# AFE_1.net
KiCad netlist of a schematic drawn in Altium Designer
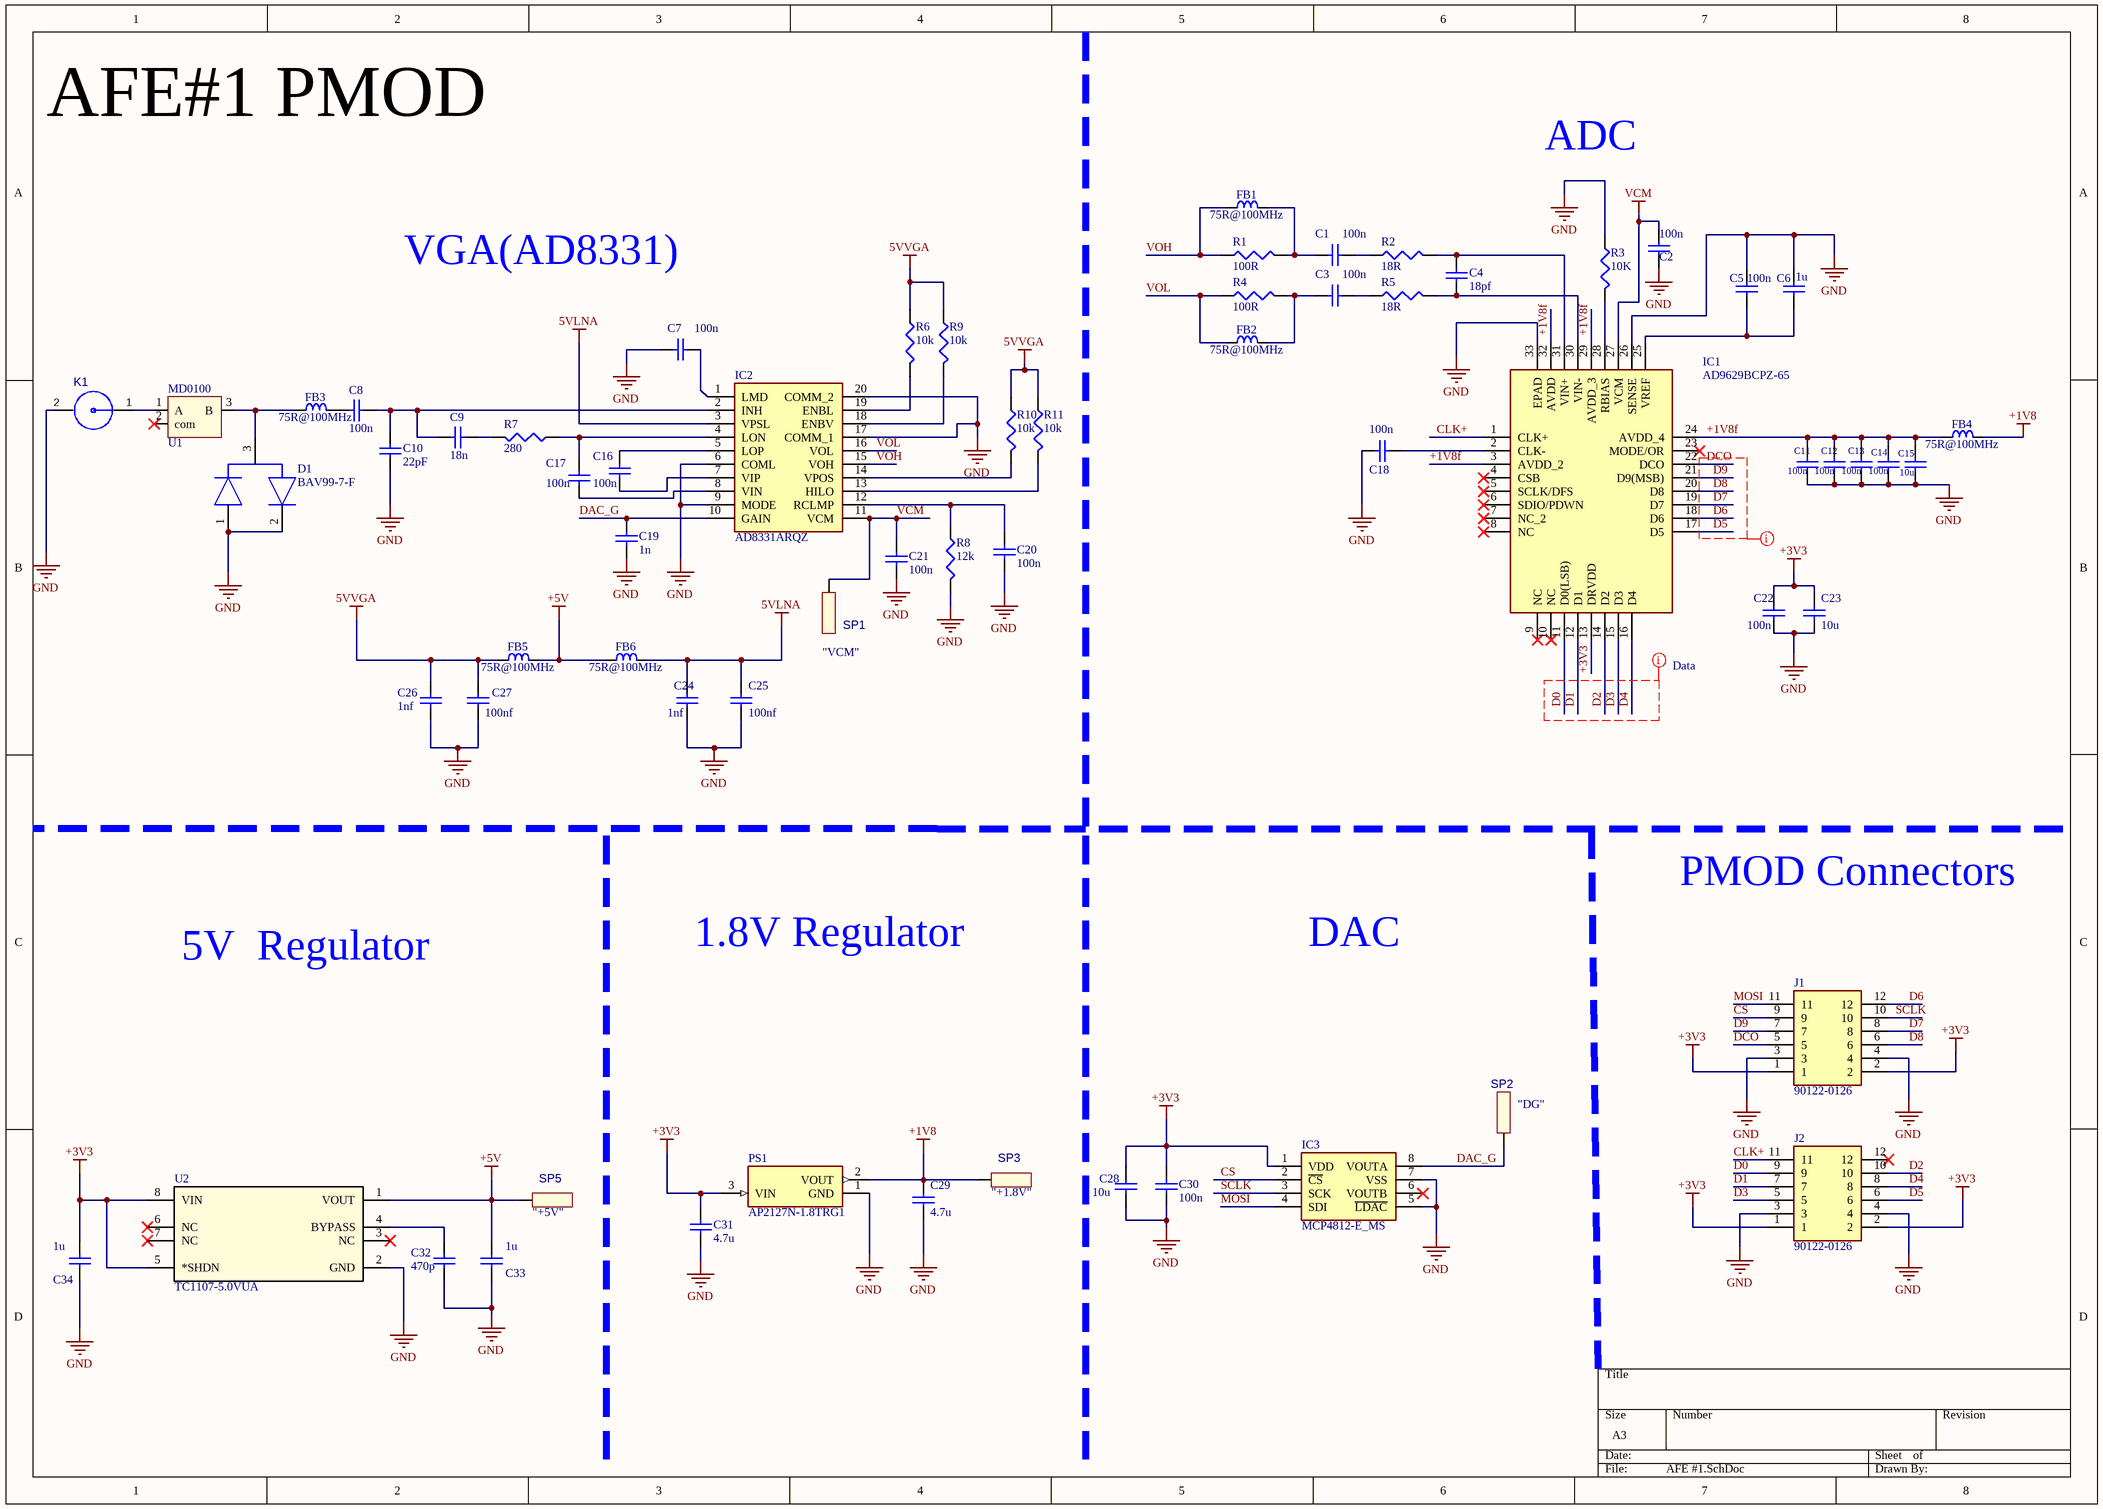
[diagram p0: AFE #1.SchDoc]

(export (version "E")
  (design (tool "Eeschema 10.0.6"))
  (components
    (comp (ref "C1")
      (value "100n")
      (footprint "0402_C")
      (description "Capacitor  0402 inch")
      (fields (field (name "Comment") "cap0402") (field (name "PUBLISHER") "Altium Limited"))
      (libsource (lib "alt2017") (part "cap0603"))
    )
    (comp (ref "C2")
      (value "100n")
      (footprint "0402_C")
      (description "Capacitor  0402 inch")
      (fields (field (name "Comment") "cap0402") (field (name "PUBLISHER") "Altium Limited"))
      (libsource (lib "alt2017") (part "cap0603"))
    )
    (comp (ref "C3")
      (value "100n")
      (footprint "0402_C")
      (description "Capacitor  0402 inch")
      (fields (field (name "Comment") "cap0402") (field (name "PUBLISHER") "Altium Limited"))
      (libsource (lib "alt2017") (part "cap0603"))
    )
    (comp (ref "C4")
      (value "18pf")
      (footprint "0402_C")
      (description "Capacitor  0402 inch")
      (fields (field (name "Comment") "cap0402") (field (name "PUBLISHER") "Altium Limited"))
      (libsource (lib "alt2017") (part "cap0603"))
    )
    (comp (ref "C5")
      (value "100n")
      (footprint "0402_C")
      (description "Capacitor  0402 inch")
      (fields (field (name "Comment") "cap0402") (field (name "PUBLISHER") "Altium Limited"))
      (libsource (lib "alt2017") (part "cap0603"))
    )
    (comp (ref "C6")
      (value "1u")
      (footprint "SM0603 _3D_cap")
      (description "Capacitor  0603 inch")
      (fields (field (name "Comment") "cap0603") (field (name "PUBLISHER") "Altium Limited"))
      (libsource (lib "alt2017") (part "cap0603"))
    )
    (comp (ref "C7")
      (value "100n")
      (footprint "0402_C")
      (description "Capacitor  0402 inch")
      (fields (field (name "Comment") "cap0402") (field (name "PUBLISHER") "Altium Limited"))
      (libsource (lib "alt2017") (part "cap0603"))
    )
    (comp (ref "C8")
      (value "100n")
      (footprint "0402_C")
      (description "Capacitor  0402 inch")
      (fields (field (name "Comment") "cap0402") (field (name "PUBLISHER") "Altium Limited"))
      (libsource (lib "alt2017") (part "cap0603"))
    )
    (comp (ref "C9")
      (value "18n")
      (footprint "0402_C")
      (description "Capacitor  0402 inch")
      (fields (field (name "Comment") "cap0402") (field (name "PUBLISHER") "Altium Limited"))
      (libsource (lib "alt2017") (part "cap0603"))
    )
    (comp (ref "C10")
      (value "22pF")
      (footprint "0402_C")
      (description "Capacitor  0402 inch")
      (fields (field (name "Comment") "cap0402") (field (name "PUBLISHER") "Altium Limited"))
      (libsource (lib "alt2017") (part "cap0603"))
    )
    (comp (ref "C11")
      (value "100n")
      (footprint "0402_C")
      (description "Capacitor  0402 inch")
      (fields (field (name "Comment") "cap0402") (field (name "PUBLISHER") "Altium Limited"))
      (libsource (lib "alt2017") (part "cap0603"))
    )
    (comp (ref "C12")
      (value "100n")
      (footprint "0402_C")
      (description "Capacitor  0402 inch")
      (fields (field (name "Comment") "cap0402") (field (name "PUBLISHER") "Altium Limited"))
      (libsource (lib "alt2017") (part "cap0603"))
    )
    (comp (ref "C13")
      (value "100n")
      (footprint "0402_C")
      (description "Capacitor  0402 inch")
      (fields (field (name "Comment") "cap0402") (field (name "PUBLISHER") "Altium Limited"))
      (libsource (lib "alt2017") (part "cap0603"))
    )
    (comp (ref "C14")
      (value "100n")
      (footprint "0402_C")
      (description "Capacitor  0402 inch")
      (fields (field (name "Comment") "cap0402") (field (name "PUBLISHER") "Altium Limited"))
      (libsource (lib "alt2017") (part "cap0603"))
    )
    (comp (ref "C15")
      (value "10u")
      (footprint "SM0603 _3D_cap")
      (description "Capacitor  0402 inch")
      (fields (field (name "Comment") "cap0402") (field (name "PUBLISHER") "Altium Limited"))
      (libsource (lib "alt2017") (part "cap0603"))
    )
    (comp (ref "C16")
      (value "100n")
      (footprint "0402_C")
      (description "Capacitor  0402 inch")
      (fields (field (name "Comment") "cap0402") (field (name "PUBLISHER") "Altium Limited"))
      (libsource (lib "alt2017") (part "cap0603"))
    )
    (comp (ref "C17")
      (value "100n")
      (footprint "0402_C")
      (description "Capacitor  0402 inch")
      (fields (field (name "Comment") "cap0402") (field (name "PUBLISHER") "Altium Limited"))
      (libsource (lib "alt2017") (part "cap0603"))
    )
    (comp (ref "C18")
      (value "100n")
      (footprint "0402_C")
      (description "Capacitor  0402 inch")
      (fields (field (name "Comment") "cap0402") (field (name "PUBLISHER") "Altium Limited"))
      (libsource (lib "alt2017") (part "cap0603"))
    )
    (comp (ref "C19")
      (value "1n")
      (footprint "0402_C")
      (description "Capacitor  0402 inch")
      (fields (field (name "Comment") "cap0402") (field (name "PUBLISHER") "Altium Limited"))
      (libsource (lib "alt2017") (part "cap0603"))
    )
    (comp (ref "C20")
      (value "100n")
      (footprint "0402_C")
      (description "Capacitor  0402 inch")
      (fields (field (name "Comment") "cap0402") (field (name "PUBLISHER") "Altium Limited"))
      (libsource (lib "alt2017") (part "cap0603"))
    )
    (comp (ref "C21")
      (value "100n")
      (footprint "0402_C")
      (description "Capacitor  0402 inch")
      (fields (field (name "Comment") "cap0402") (field (name "PUBLISHER") "Altium Limited"))
      (libsource (lib "alt2017") (part "cap0603"))
    )
    (comp (ref "C22")
      (value "100n")
      (footprint "0402_C")
      (description "Capacitor  0402 inch")
      (fields (field (name "Comment") "cap0402") (field (name "PUBLISHER") "Altium Limited"))
      (libsource (lib "alt2017") (part "cap0603"))
    )
    (comp (ref "C23")
      (value "10u")
      (footprint "SM0603 _3D_cap")
      (description "Capacitor  0603 inch")
      (fields (field (name "Comment") "cap0603") (field (name "PUBLISHER") "Altium Limited"))
      (libsource (lib "alt2017") (part "cap0603"))
    )
    (comp (ref "C24")
      (value "1nf")
      (footprint "0402_C")
      (description "Capacitor  0603 inch")
      (fields (field (name "Comment") "cap0402") (field (name "PUBLISHER") "Altium Limited"))
      (libsource (lib "alt2017") (part "cap0603"))
    )
    (comp (ref "C25")
      (value "100nf")
      (footprint "0402_C")
      (description "Capacitor  0402 inch")
      (fields (field (name "Comment") "cap0402") (field (name "PUBLISHER") "Altium Limited"))
      (libsource (lib "alt2017") (part "cap0603"))
    )
    (comp (ref "C26")
      (value "1nf")
      (footprint "0402_C")
      (description "Capacitor  0603 inch")
      (fields (field (name "Comment") "cap0402") (field (name "PUBLISHER") "Altium Limited"))
      (libsource (lib "alt2017") (part "cap0603"))
    )
    (comp (ref "C27")
      (value "100nf")
      (footprint "0402_C")
      (description "Capacitor  0402 inch")
      (fields (field (name "Comment") "cap0402") (field (name "PUBLISHER") "Altium Limited"))
      (libsource (lib "alt2017") (part "cap0603"))
    )
    (comp (ref "C28")
      (value "10u")
      (footprint "SM0603 _3D_cap")
      (description "Capacitor  0603 inch")
      (fields (field (name "Comment") "cap0603") (field (name "PUBLISHER") "Altium Limited"))
      (libsource (lib "alt2017") (part "cap0603"))
    )
    (comp (ref "C29")
      (value "4.7u")
      (footprint "SM0603 _3D_cap")
      (description "Capacitor  0603 inch")
      (fields (field (name "Comment") "cap0603") (field (name "PUBLISHER") "Altium Limited"))
      (libsource (lib "alt2017") (part "cap0603"))
    )
    (comp (ref "C30")
      (value "100n")
      (footprint "0402_C")
      (description "Capacitor  0402 inch")
      (fields (field (name "Comment") "cap0402") (field (name "PUBLISHER") "Altium Limited"))
      (libsource (lib "alt2017") (part "cap0603"))
    )
    (comp (ref "C31")
      (value "4.7u")
      (footprint "SM0603 _3D_cap")
      (description "Capacitor  0603 inch")
      (fields (field (name "Comment") "cap0603") (field (name "PUBLISHER") "Altium Limited"))
      (libsource (lib "alt2017") (part "cap0603"))
    )
    (comp (ref "C32")
      (value "470p")
      (footprint "0402_C")
      (description "Capacitor  0402 inch")
      (fields (field (name "Comment") "cap0402") (field (name "PUBLISHER") "Altium Limited"))
      (libsource (lib "alt2017") (part "cap0603"))
    )
    (comp (ref "C33")
      (value "1u")
      (footprint "SM0603 _3D_cap")
      (description "Capacitor  0603 inch")
      (fields (field (name "Comment") "cap0603") (field (name "PUBLISHER") "Altium Limited"))
      (libsource (lib "alt2017") (part "cap0603"))
    )
    (comp (ref "C34")
      (value "1u")
      (footprint "SM0603 _3D_cap")
      (description "Capacitor  0603 inch")
      (fields (field (name "Comment") "cap0603") (field (name "PUBLISHER") "Altium Limited"))
      (libsource (lib "alt2017") (part "cap0603"))
    )
    (comp (ref "D1")
      (value "BAV99-7-F")
      (footprint "SOT95P240X120-3N")
      (description "Diode")
      (fields (field (name "MOUSER PART NUMBER") "621-BAV99-F"))
      (libsource (lib "*") (part "BAV99-7-F"))
    )
    (comp (ref "FB1")
      (value "75R@100MHz")
      (footprint "SM0603_3D_res")
      (description "chip inductance 0603")
      (fields
        (field (name "PART NUMBER") "IND0805_MURATA_BLM21BB750SN1D")
        (field (name "POWER") "700mA")
        (field (name "AUTHOR") "S. Jafar")
      )
      (libsource (lib "alt_vovan") (part "chip inductance 0603"))
    )
    (comp (ref "FB2")
      (value "75R@100MHz")
      (footprint "SM0603_3D_res")
      (description "chip inductance 0603")
      (fields
        (field (name "PART NUMBER") "IND0805_MURATA_BLM21BB750SN1D")
        (field (name "POWER") "700mA")
        (field (name "AUTHOR") "S. Jafar")
      )
      (libsource (lib "alt_vovan") (part "chip inductance 0603"))
    )
    (comp (ref "FB3")
      (value "75R@100MHz")
      (footprint "SM0603_3D_res")
      (description "chip inductance 0603")
      (fields
        (field (name "PART NUMBER") "IND0805_MURATA_BLM21BB750SN1D")
        (field (name "POWER") "700mA")
        (field (name "AUTHOR") "S. Jafar")
      )
      (libsource (lib "alt_vovan") (part "chip inductance 0603"))
    )
    (comp (ref "FB4")
      (value "75R@100MHz")
      (footprint "SM0603_3D_res")
      (description "chip inductance 0603")
      (fields
        (field (name "PART NUMBER") "IND0805_MURATA_BLM21BB750SN1D")
        (field (name "POWER") "700mA")
        (field (name "AUTHOR") "S. Jafar")
      )
      (libsource (lib "alt_vovan") (part "chip inductance 0603"))
    )
    (comp (ref "FB5")
      (value "75R@100MHz")
      (footprint "SM0603_3D_res")
      (description "chip inductance 0603")
      (fields
        (field (name "PART NUMBER") "IND0805_MURATA_BLM21BB750SN1D")
        (field (name "POWER") "700mA")
        (field (name "AUTHOR") "S. Jafar")
      )
      (libsource (lib "alt_vovan") (part "chip inductance 0603"))
    )
    (comp (ref "FB6")
      (value "75R@100MHz")
      (footprint "SM0603_3D_res")
      (description "chip inductance 0603")
      (fields
        (field (name "PART NUMBER") "IND0805_MURATA_BLM21BB750SN1D")
        (field (name "POWER") "700mA")
        (field (name "AUTHOR") "S. Jafar")
      )
      (libsource (lib "alt_vovan") (part "chip inductance 0603"))
    )
    (comp (ref "IC1")
      (value "AD9629BCPZ-65")
      (footprint "QFN50P500X500X100-33N")
      (description "Integrated Circuit")
      (fields (field (name "MOUSER PART NUMBER") "584-AD9629BCPZ-65"))
      (libsource (lib "AFE# 1") (part "AD9629BCPZ-65"))
    )
    (comp (ref "IC2")
      (value "AD8331ARQZ")
      (footprint "SOP64P600X175-20N")
      (description "Integrated Circuit")
      (fields (field (name "MOUSER PART NUMBER") "584-AD8331ARQZ"))
      (libsource (lib "*") (part "AD8331ARQZ"))
    )
    (comp (ref "IC3")
      (value "MCP4812-E_MS")
      (footprint "shunt_resistor:SOP65P490X110-8N")
      (description "Integrated Circuit")
      (fields
        (field (name "MANUFACTURER_PART_NUMBER") "MCP4812-E/MS")
        (field (name "MOUSER PART NUMBER") "579-MCP4812-E/MS")
      )
      (libsource (lib "*") (part "MCP4812-E_MS"))
    )
    (comp (ref "J1")
      (value "90122-0126")
      (footprint "shunt_resistor:HDRRA12W65P254_2X6_1516X250X615P")
      (description "Connector")
      (fields (field (name "MOUSER PART NUMBER") "538-90122-0126"))
      (libsource (lib "*") (part "90122-0126"))
    )
    (comp (ref "J2")
      (value "90122-0126")
      (footprint "shunt_resistor:HDRRA12W65P254_2X6_1516X250X615P")
      (description "Connector")
      (fields (field (name "MOUSER PART NUMBER") "538-90122-0126"))
      (libsource (lib "*") (part "90122-0126"))
    )
    (comp (ref "K1")
      (value "SMA_Edge")
      (footprint "AMPHENOL_132357-11")
      (libsource (lib "alt2017") (part "SMA_Edge"))
    )
    (comp (ref "PS1")
      (value "AP2127N-1.8TRG1")
      (footprint "SOT89P240X110-3N")
      (description "Power Supply")
      (fields
        (field (name "MANUFACTURER_PART_NUMBER") "AP2127N-3.3TRG1")
        (field (name "MOUSER PART NUMBER") "621-AP2127N-3.3TRG1")
      )
      (libsource (lib "*") (part "AP2127N-3.3TRG1"))
    )
    (comp (ref "R1")
      (value "100R")
      (footprint "0402_R")
      (description "RES 10K OHM 1/16W 0402 SMD")
      (libsource (lib "Integrated_Library_RF_FEB_2012") (part "RC0402FR-0710KL"))
    )
    (comp (ref "R2")
      (value "18R")
      (footprint "0402_R")
      (description "RES 18 OHM 1/16W 0402 SMD")
      (libsource (lib "Integrated_Library_RF_FEB_2012") (part "RC0402FR-0710KL"))
    )
    (comp (ref "R3")
      (value "10K")
      (footprint "0402_R")
      (description "RES 10K OHM 1/16W 0402 SMD")
      (libsource (lib "Integrated_Library_RF_FEB_2012") (part "RC0402FR-0710KL"))
    )
    (comp (ref "R4")
      (value "100R")
      (footprint "0402_R")
      (description "RES 10K OHM 1/16W 0402 SMD")
      (libsource (lib "Integrated_Library_RF_FEB_2012") (part "RC0402FR-0710KL"))
    )
    (comp (ref "R5")
      (value "18R")
      (footprint "0402_R")
      (description "RES 18 OHM 1/16W 0402 SMD")
      (libsource (lib "Integrated_Library_RF_FEB_2012") (part "RC0402FR-0710KL"))
    )
    (comp (ref "R6")
      (value "10k")
      (footprint "0402_R")
      (description "RES 10K OHM 1/16W 1% 0402 SMD")
      (libsource (lib "Integrated_Library_RF_FEB_2012") (part "RC0402FR-0710KL"))
    )
    (comp (ref "R7")
      (value "280")
      (footprint "0402_R")
      (description "RES 280 OHM 1/16W 0402 SMD")
      (libsource (lib "Integrated_Library_RF_FEB_2012") (part "RC0402FR-0710KL"))
    )
    (comp (ref "R8")
      (value "12k")
      (footprint "0402_R")
      (description "RES 12K OHM 1/16W 0402 SMD")
      (libsource (lib "Integrated_Library_RF_FEB_2012") (part "RC0402FR-0710KL"))
    )
    (comp (ref "R9")
      (value "10k")
      (footprint "0402_R")
      (description "RES 10K OHM 1/16W 1% 0402 SMD")
      (libsource (lib "Integrated_Library_RF_FEB_2012") (part "RC0402FR-0710KL"))
    )
    (comp (ref "R10")
      (value "10k")
      (footprint "0402_R")
      (description "RES 10K OHM 1/16W 1% 0402 SMD")
      (libsource (lib "Integrated_Library_RF_FEB_2012") (part "RC0402FR-0710KL"))
    )
    (comp (ref "R11")
      (value "10k")
      (footprint "0402_R")
      (description "RES 10K OHM 1/16W 1% 0402 SMD")
      (libsource (lib "Integrated_Library_RF_FEB_2012") (part "RC0402FR-0710KL"))
    )
    (comp (ref "SP1")
      (value "\"VCM\"")
      (footprint "SolderPad_D1mm _round")
      (description "for finger touch")
      (fields (field (name "Comment") "SolderPad D1mm_round"))
      (libsource (lib "alt2017") (part "SolderPad D1mm_round"))
    )
    (comp (ref "SP2")
      (value "\"DG\"")
      (footprint "SolderPad_D1mm _round")
      (description "for finger touch")
      (fields (field (name "Comment") "SolderPad D1mm_round"))
      (libsource (lib "") (part "SolderPad D1mm_round_2"))
    )
    (comp (ref "SP3")
      (value "\"+1.8V\"")
      (footprint "SolderPad_D1mm _round")
      (description "for finger touch")
      (fields (field (name "Comment") "SolderPad D1mm_round"))
      (libsource (lib "") (part "SolderPad D1mm_round_1"))
    )
    (comp (ref "SP5")
      (value "\"+5V\"")
      (footprint "SolderPad_D1mm _round")
      (description "for finger touch")
      (fields (field (name "Comment") "SolderPad D1mm_round"))
      (libsource (lib "") (part "SolderPad D1mm_round_1"))
    )
    (comp (ref "U1")
      (value "T/R switch")
      (footprint "SOT89-150P409X160-3N")
      (libsource (lib "alt_vovan") (part "MD0100N8-G"))
    )
    (comp (ref "U2")
      (value "TC1107-5.0VUA")
      (footprint "MSOP8_MC_MCH_")
      (description "No Description Available")
      (fields (field (name "COPYRIGHT") "Copyright (C) 2022 Ultra Librarian. All rights reserved."))
      (libsource (lib "TC1107-5P0VUA") (part "TC1107-5.0VUA"))
    )
  )
  (nets
    (net (code "1") (name "+1V8") (class "Default")
      (node (ref "C29") (pin "1") (pinfunction "1_1") (pintype "passive"))
      (node (ref "FB4") (pin "2") (pinfunction "2_2") (pintype "passive"))
      (node (ref "PS1") (pin "2") (pinfunction "VOUT_2") (pintype "output"))
      (node (ref "SP3") (pin "1") (pinfunction "1_1") (pintype "passive"))
    )
    (net (code "2") (name "+3V3") (class "Default")
      (node (ref "C22") (pin "1") (pinfunction "1_1") (pintype "passive"))
      (node (ref "C23") (pin "1") (pinfunction "1_1") (pintype "passive"))
      (node (ref "C28") (pin "1") (pinfunction "1_1") (pintype "passive"))
      (node (ref "C30") (pin "1") (pinfunction "1_1") (pintype "passive"))
      (node (ref "C31") (pin "2") (pinfunction "2_2") (pintype "passive"))
      (node (ref "C34") (pin "1") (pinfunction "1_1") (pintype "passive"))
      (node (ref "IC1") (pin "13") (pinfunction "DRVDD_13") (pintype "passive"))
      (node (ref "IC3") (pin "1") (pinfunction "VDD_1") (pintype "passive"))
      (node (ref "J1") (pin "1") (pinfunction "1_1") (pintype "passive"))
      (node (ref "J1") (pin "2") (pinfunction "2_2") (pintype "passive"))
      (node (ref "J2") (pin "1") (pinfunction "1_1") (pintype "passive"))
      (node (ref "J2") (pin "2") (pinfunction "2_2") (pintype "passive"))
      (node (ref "PS1") (pin "3") (pinfunction "VIN_3") (pintype "input"))
      (node (ref "U2") (pin "5") (pinfunction "*SHDN_5") (pintype "passive"))
      (node (ref "U2") (pin "8") (pinfunction "VIN_8") (pintype "passive"))
    )
    (net (code "3") (name "+5V") (class "Default")
      (node (ref "C33") (pin "1") (pinfunction "1_1") (pintype "passive"))
      (node (ref "FB5") (pin "2") (pinfunction "2_2") (pintype "passive"))
      (node (ref "FB6") (pin "1") (pinfunction "1_1") (pintype "passive"))
      (node (ref "SP5") (pin "1") (pinfunction "1_1") (pintype "passive"))
      (node (ref "U2") (pin "1") (pinfunction "VOUT_1") (pintype "passive"))
    )
    (net (code "4") (name "/+1V8f") (class "Default")
      (node (ref "C11") (pin "1") (pinfunction "1_1") (pintype "passive"))
      (node (ref "C12") (pin "1") (pinfunction "1_1") (pintype "passive"))
      (node (ref "C13") (pin "1") (pinfunction "1_1") (pintype "passive"))
      (node (ref "C14") (pin "1") (pinfunction "1_1") (pintype "passive"))
      (node (ref "C15") (pin "1") (pinfunction "1_1") (pintype "passive"))
      (node (ref "FB4") (pin "1") (pinfunction "1_1") (pintype "passive"))
      (node (ref "IC1") (pin "24") (pinfunction "AVDD_4_24") (pintype "passive"))
      (node (ref "IC1") (pin "29") (pinfunction "AVDD_3_29") (pintype "passive"))
      (node (ref "IC1") (pin "3") (pinfunction "AVDD_2_3") (pintype "passive"))
      (node (ref "IC1") (pin "32") (pinfunction "AVDD_32") (pintype "passive"))
    )
    (net (code "5") (name "/CLK+") (class "Default")
      (node (ref "IC1") (pin "1") (pinfunction "CLK+_1") (pintype "passive"))
      (node (ref "J2") (pin "11") (pinfunction "11_11") (pintype "passive"))
    )
    (net (code "6") (name "/CS") (class "Default")
      (node (ref "IC3") (pin "2") (pinfunction "~{CS}_2") (pintype "passive"))
      (node (ref "J1") (pin "9") (pinfunction "9_9") (pintype "passive"))
    )
    (net (code "7") (name "/D0") (class "Default")
      (node (ref "IC1") (pin "11") (pinfunction "D0(LSB)_11") (pintype "passive"))
      (node (ref "J2") (pin "9") (pinfunction "9_9") (pintype "passive"))
    )
    (net (code "8") (name "/D1") (class "Default")
      (node (ref "IC1") (pin "12") (pinfunction "D1_12") (pintype "passive"))
      (node (ref "J2") (pin "7") (pinfunction "7_7") (pintype "passive"))
    )
    (net (code "9") (name "/D2") (class "Default")
      (node (ref "IC1") (pin "14") (pinfunction "D2_14") (pintype "passive"))
      (node (ref "J2") (pin "10") (pinfunction "10_10") (pintype "passive"))
    )
    (net (code "10") (name "/D3") (class "Default")
      (node (ref "IC1") (pin "15") (pinfunction "D3_15") (pintype "passive"))
      (node (ref "J2") (pin "5") (pinfunction "5_5") (pintype "passive"))
    )
    (net (code "11") (name "/D4") (class "Default")
      (node (ref "IC1") (pin "16") (pinfunction "D4_16") (pintype "passive"))
      (node (ref "J2") (pin "8") (pinfunction "8_8") (pintype "passive"))
    )
    (net (code "12") (name "/D5") (class "Default")
      (node (ref "IC1") (pin "17") (pinfunction "D5_17") (pintype "passive"))
      (node (ref "J2") (pin "6") (pinfunction "6_6") (pintype "passive"))
    )
    (net (code "13") (name "/D6") (class "Default")
      (node (ref "IC1") (pin "18") (pinfunction "D6_18") (pintype "passive"))
      (node (ref "J1") (pin "12") (pinfunction "12_12") (pintype "passive"))
    )
    (net (code "14") (name "/D7") (class "Default")
      (node (ref "IC1") (pin "19") (pinfunction "D7_19") (pintype "passive"))
      (node (ref "J1") (pin "8") (pinfunction "8_8") (pintype "passive"))
    )
    (net (code "15") (name "/D8") (class "Default")
      (node (ref "IC1") (pin "20") (pinfunction "D8_20") (pintype "passive"))
      (node (ref "J1") (pin "6") (pinfunction "6_6") (pintype "passive"))
    )
    (net (code "16") (name "/D9") (class "Default")
      (node (ref "IC1") (pin "21") (pinfunction "D9(MSB)_21") (pintype "passive"))
      (node (ref "J1") (pin "7") (pinfunction "7_7") (pintype "passive"))
    )
    (net (code "17") (name "/DAC_G") (class "Default")
      (node (ref "C19") (pin "2") (pinfunction "2_2") (pintype "passive"))
      (node (ref "IC2") (pin "10") (pinfunction "GAIN_10") (pintype "passive"))
      (node (ref "IC3") (pin "8") (pinfunction "VOUTA_8") (pintype "passive"))
      (node (ref "SP2") (pin "1") (pinfunction "1_1") (pintype "passive"))
    )
    (net (code "18") (name "/DCO") (class "Default")
      (node (ref "IC1") (pin "22") (pinfunction "DCO_22") (pintype "passive"))
      (node (ref "J1") (pin "5") (pinfunction "5_5") (pintype "passive"))
    )
    (net (code "19") (name "/MOSI") (class "Default")
      (node (ref "IC3") (pin "4") (pinfunction "SDI_4") (pintype "passive"))
      (node (ref "J1") (pin "11") (pinfunction "11_11") (pintype "passive"))
    )
    (net (code "20") (name "/SCLK") (class "Default")
      (node (ref "IC3") (pin "3") (pinfunction "SCK_3") (pintype "passive"))
      (node (ref "J1") (pin "10") (pinfunction "10_10") (pintype "passive"))
    )
    (net (code "21") (name "/VOH") (class "Default")
      (node (ref "FB1") (pin "1") (pinfunction "1_1") (pintype "passive"))
      (node (ref "IC2") (pin "15") (pinfunction "VOH_15") (pintype "passive"))
      (node (ref "R1") (pin "1") (pinfunction "1_1") (pintype "passive"))
    )
    (net (code "22") (name "/VOL") (class "Default")
      (node (ref "FB2") (pin "1") (pinfunction "1_1") (pintype "passive"))
      (node (ref "IC2") (pin "16") (pinfunction "VOL_16") (pintype "passive"))
      (node (ref "R4") (pin "1") (pinfunction "1_1") (pintype "passive"))
    )
    (net (code "23") (name "5VLNA") (class "Default")
      (node (ref "C24") (pin "2") (pinfunction "2_2") (pintype "passive"))
      (node (ref "C25") (pin "2") (pinfunction "2_2") (pintype "passive"))
      (node (ref "FB6") (pin "2") (pinfunction "2_2") (pintype "passive"))
      (node (ref "IC2") (pin "3") (pinfunction "VPSL_3") (pintype "passive"))
    )
    (net (code "24") (name "5VVGA") (class "Default")
      (node (ref "C26") (pin "2") (pinfunction "2_2") (pintype "passive"))
      (node (ref "C27") (pin "2") (pinfunction "2_2") (pintype "passive"))
      (node (ref "FB5") (pin "1") (pinfunction "1_1") (pintype "passive"))
      (node (ref "R10") (pin "1") (pinfunction "1_1") (pintype "passive"))
      (node (ref "R11") (pin "1") (pinfunction "1_1") (pintype "passive"))
      (node (ref "R6") (pin "1") (pinfunction "1_1") (pintype "passive"))
      (node (ref "R9") (pin "1") (pinfunction "1_1") (pintype "passive"))
    )
    (net (code "25") (name "GND") (class "Default")
      (node (ref "C10") (pin "1") (pinfunction "1_1") (pintype "passive"))
      (node (ref "C11") (pin "2") (pinfunction "2_2") (pintype "passive"))
      (node (ref "C12") (pin "2") (pinfunction "2_2") (pintype "passive"))
      (node (ref "C13") (pin "2") (pinfunction "2_2") (pintype "passive"))
      (node (ref "C14") (pin "2") (pinfunction "2_2") (pintype "passive"))
      (node (ref "C15") (pin "2") (pinfunction "2_2") (pintype "passive"))
      (node (ref "C18") (pin "2") (pinfunction "2_2") (pintype "passive"))
      (node (ref "C19") (pin "1") (pinfunction "1_1") (pintype "passive"))
      (node (ref "C2") (pin "2") (pinfunction "2_2") (pintype "passive"))
      (node (ref "C20") (pin "1") (pinfunction "1_1") (pintype "passive"))
      (node (ref "C21") (pin "2") (pinfunction "2_2") (pintype "passive"))
      (node (ref "C22") (pin "2") (pinfunction "2_2") (pintype "passive"))
      (node (ref "C23") (pin "2") (pinfunction "2_2") (pintype "passive"))
      (node (ref "C24") (pin "1") (pinfunction "1_1") (pintype "passive"))
      (node (ref "C25") (pin "1") (pinfunction "1_1") (pintype "passive"))
      (node (ref "C26") (pin "1") (pinfunction "1_1") (pintype "passive"))
      (node (ref "C27") (pin "1") (pinfunction "1_1") (pintype "passive"))
      (node (ref "C28") (pin "2") (pinfunction "2_2") (pintype "passive"))
      (node (ref "C29") (pin "2") (pinfunction "2_2") (pintype "passive"))
      (node (ref "C30") (pin "2") (pinfunction "2_2") (pintype "passive"))
      (node (ref "C31") (pin "1") (pinfunction "1_1") (pintype "passive"))
      (node (ref "C32") (pin "1") (pinfunction "1_1") (pintype "passive"))
      (node (ref "C33") (pin "2") (pinfunction "2_2") (pintype "passive"))
      (node (ref "C34") (pin "2") (pinfunction "2_2") (pintype "passive"))
      (node (ref "C5") (pin "1") (pinfunction "1_1") (pintype "passive"))
      (node (ref "C6") (pin "1") (pinfunction "1_1") (pintype "passive"))
      (node (ref "C7") (pin "1") (pinfunction "1_1") (pintype "passive"))
      (node (ref "D1") (pin "1") (pinfunction "ANODE_1") (pintype "passive"))
      (node (ref "D1") (pin "2") (pinfunction "CATHODE_2") (pintype "passive"))
      (node (ref "IC1") (pin "26") (pinfunction "SENSE_26") (pintype "passive"))
      (node (ref "IC1") (pin "33") (pinfunction "EPAD_33") (pintype "passive"))
      (node (ref "IC2") (pin "17") (pinfunction "COMM_1_17") (pintype "passive"))
      (node (ref "IC2") (pin "20") (pinfunction "COMM_2_20") (pintype "passive"))
      (node (ref "IC2") (pin "6") (pinfunction "COML_6") (pintype "passive"))
      (node (ref "IC2") (pin "9") (pinfunction "MODE_9") (pintype "passive"))
      (node (ref "IC3") (pin "5") (pinfunction "~{LDAC}_5") (pintype "passive"))
      (node (ref "IC3") (pin "7") (pinfunction "VSS_7") (pintype "passive"))
      (node (ref "J1") (pin "3") (pinfunction "3_3") (pintype "passive"))
      (node (ref "J1") (pin "4") (pinfunction "4_4") (pintype "passive"))
      (node (ref "J2") (pin "3") (pinfunction "3_3") (pintype "passive"))
      (node (ref "J2") (pin "4") (pinfunction "4_4") (pintype "passive"))
      (node (ref "K1") (pin "2") (pinfunction "2_2") (pintype "passive"))
      (node (ref "PS1") (pin "1") (pinfunction "GND_1") (pintype "power_in"))
      (node (ref "R3") (pin "1") (pinfunction "1_1") (pintype "passive"))
      (node (ref "R8") (pin "2") (pinfunction "2_2") (pintype "passive"))
      (node (ref "U2") (pin "2") (pinfunction "GND_2") (pintype "passive"))
    )
    (net (code "26") (name "Net-(C1-Pad1)") (class "Default")
      (node (ref "C1") (pin "1") (pinfunction "1_1") (pintype "passive"))
      (node (ref "R2") (pin "1") (pinfunction "1_1") (pintype "passive"))
    )
    (net (code "27") (name "Net-(C1-Pad2)") (class "Default")
      (node (ref "C1") (pin "2") (pinfunction "2_2") (pintype "passive"))
      (node (ref "FB1") (pin "2") (pinfunction "2_2") (pintype "passive"))
      (node (ref "R1") (pin "2") (pinfunction "2_2") (pintype "passive"))
    )
    (net (code "28") (name "Net-(C3-Pad1)") (class "Default")
      (node (ref "C3") (pin "1") (pinfunction "1_1") (pintype "passive"))
      (node (ref "R5") (pin "1") (pinfunction "1_1") (pintype "passive"))
    )
    (net (code "29") (name "Net-(C3-Pad2)") (class "Default")
      (node (ref "C3") (pin "2") (pinfunction "2_2") (pintype "passive"))
      (node (ref "FB2") (pin "2") (pinfunction "2_2") (pintype "passive"))
      (node (ref "R4") (pin "2") (pinfunction "2_2") (pintype "passive"))
    )
    (net (code "30") (name "Net-(C8-Pad1)") (class "Default")
      (node (ref "C8") (pin "1") (pinfunction "1_1") (pintype "passive"))
      (node (ref "FB3") (pin "2") (pinfunction "2_2") (pintype "passive"))
    )
    (net (code "31") (name "Net-(C9-Pad1)") (class "Default")
      (node (ref "C9") (pin "1") (pinfunction "1_1") (pintype "passive"))
      (node (ref "R7") (pin "2") (pinfunction "2_2") (pintype "passive"))
    )
    (net (code "32") (name "Net-(D1-A{slash}K)") (class "Default")
      (node (ref "D1") (pin "3") (pinfunction "A/K_3") (pintype "passive"))
      (node (ref "FB3") (pin "1") (pinfunction "1_1") (pintype "passive"))
      (node (ref "U1") (pin "3") (pinfunction "B_3") (pintype "passive"))
    )
    (net (code "33") (name "Net-(IC1-CLK-)") (class "Default")
      (node (ref "C18") (pin "1") (pinfunction "1_1") (pintype "passive"))
      (node (ref "IC1") (pin "2") (pinfunction "CLK-_2") (pintype "passive"))
    )
    (net (code "34") (name "Net-(IC1-RBIAS)") (class "Default")
      (node (ref "IC1") (pin "28") (pinfunction "RBIAS_28") (pintype "passive"))
      (node (ref "R3") (pin "2") (pinfunction "2_2") (pintype "passive"))
    )
    (net (code "35") (name "Net-(IC1-VIN+)") (class "Default")
      (node (ref "C4") (pin "1") (pinfunction "1_1") (pintype "passive"))
      (node (ref "IC1") (pin "31") (pinfunction "VIN+_31") (pintype "passive"))
      (node (ref "R2") (pin "2") (pinfunction "2_2") (pintype "passive"))
    )
    (net (code "36") (name "Net-(IC1-VIN-)") (class "Default")
      (node (ref "C4") (pin "2") (pinfunction "2_2") (pintype "passive"))
      (node (ref "IC1") (pin "30") (pinfunction "VIN-_30") (pintype "passive"))
      (node (ref "R5") (pin "2") (pinfunction "2_2") (pintype "passive"))
    )
    (net (code "37") (name "Net-(IC1-VREF)") (class "Default")
      (node (ref "C5") (pin "2") (pinfunction "2_2") (pintype "passive"))
      (node (ref "C6") (pin "2") (pinfunction "2_2") (pintype "passive"))
      (node (ref "IC1") (pin "25") (pinfunction "VREF_25") (pintype "passive"))
    )
    (net (code "38") (name "Net-(IC2-ENBL)") (class "Default")
      (node (ref "IC2") (pin "19") (pinfunction "ENBL_19") (pintype "passive"))
      (node (ref "R6") (pin "2") (pinfunction "2_2") (pintype "passive"))
    )
    (net (code "39") (name "Net-(IC2-ENBV)") (class "Default")
      (node (ref "IC2") (pin "18") (pinfunction "ENBV_18") (pintype "passive"))
      (node (ref "R9") (pin "2") (pinfunction "2_2") (pintype "passive"))
    )
    (net (code "40") (name "Net-(IC2-HILO)") (class "Default")
      (node (ref "IC2") (pin "13") (pinfunction "HILO_13") (pintype "passive"))
      (node (ref "R11") (pin "2") (pinfunction "2_2") (pintype "passive"))
    )
    (net (code "41") (name "Net-(IC2-INH)") (class "Default")
      (node (ref "C10") (pin "2") (pinfunction "2_2") (pintype "passive"))
      (node (ref "C8") (pin "2") (pinfunction "2_2") (pintype "passive"))
      (node (ref "C9") (pin "2") (pinfunction "2_2") (pintype "passive"))
      (node (ref "IC2") (pin "2") (pinfunction "INH_2") (pintype "passive"))
    )
    (net (code "42") (name "Net-(IC2-LMD)") (class "Default")
      (node (ref "C7") (pin "2") (pinfunction "2_2") (pintype "passive"))
      (node (ref "IC2") (pin "1") (pinfunction "LMD_1") (pintype "passive"))
    )
    (net (code "43") (name "Net-(IC2-LON)") (class "Default")
      (node (ref "C17") (pin "2") (pinfunction "2_2") (pintype "passive"))
      (node (ref "IC2") (pin "4") (pinfunction "LON_4") (pintype "passive"))
      (node (ref "R7") (pin "1") (pinfunction "1_1") (pintype "passive"))
    )
    (net (code "44") (name "Net-(IC2-LOP)") (class "Default")
      (node (ref "C16") (pin "2") (pinfunction "2_2") (pintype "passive"))
      (node (ref "IC2") (pin "5") (pinfunction "LOP_5") (pintype "passive"))
    )
    (net (code "45") (name "Net-(IC2-RCLMP)") (class "Default")
      (node (ref "C20") (pin "2") (pinfunction "2_2") (pintype "passive"))
      (node (ref "IC2") (pin "12") (pinfunction "RCLMP_12") (pintype "passive"))
      (node (ref "R8") (pin "1") (pinfunction "1_1") (pintype "passive"))
    )
    (net (code "46") (name "Net-(IC2-VIN)") (class "Default")
      (node (ref "C17") (pin "1") (pinfunction "1_1") (pintype "passive"))
      (node (ref "IC2") (pin "8") (pinfunction "VIN_8") (pintype "passive"))
    )
    (net (code "47") (name "Net-(IC2-VIP)") (class "Default")
      (node (ref "C16") (pin "1") (pinfunction "1_1") (pintype "passive"))
      (node (ref "IC2") (pin "7") (pinfunction "VIP_7") (pintype "passive"))
    )
    (net (code "48") (name "Net-(IC2-VPOS)") (class "Default")
      (node (ref "IC2") (pin "14") (pinfunction "VPOS_14") (pintype "passive"))
      (node (ref "R10") (pin "2") (pinfunction "2_2") (pintype "passive"))
    )
    (net (code "49") (name "Net-(U1-A)") (class "Default")
      (node (ref "K1") (pin "1") (pinfunction "1_1") (pintype "passive"))
      (node (ref "U1") (pin "1") (pinfunction "A_1") (pintype "passive"))
    )
    (net (code "50") (name "Net-(U2-BYPASS)") (class "Default")
      (node (ref "C32") (pin "2") (pinfunction "2_2") (pintype "passive"))
      (node (ref "U2") (pin "4") (pinfunction "BYPASS_4") (pintype "passive"))
    )
    (net (code "51") (name "VCM") (class "Default")
      (node (ref "C2") (pin "1") (pinfunction "1_1") (pintype "passive"))
      (node (ref "C21") (pin "1") (pinfunction "1_1") (pintype "passive"))
      (node (ref "IC1") (pin "27") (pinfunction "VCM_27") (pintype "passive"))
      (node (ref "IC2") (pin "11") (pinfunction "VCM_11") (pintype "passive"))
      (node (ref "SP1") (pin "1") (pinfunction "1_1") (pintype "passive"))
    )
    (net (code "52") (name "unconnected-(IC1-CSB-Pad4)") (class "Default")
      (node (ref "IC1") (pin "4") (pinfunction "CSB_4") (pintype "passive+no_connect"))
    )
    (net (code "53") (name "unconnected-(IC1-MODE{slash}OR-Pad23)") (class "Default")
      (node (ref "IC1") (pin "23") (pinfunction "MODE/OR_23") (pintype "passive+no_connect"))
    )
    (net (code "54") (name "unconnected-(IC1-NC-Pad8)") (class "Default")
      (node (ref "IC1") (pin "8") (pinfunction "NC_8") (pintype "passive+no_connect"))
    )
    (net (code "55") (name "unconnected-(IC1-NC-Pad9)") (class "Default")
      (node (ref "IC1") (pin "9") (pinfunction "NC_9") (pintype "passive+no_connect"))
    )
    (net (code "56") (name "unconnected-(IC1-NC-Pad10)") (class "Default")
      (node (ref "IC1") (pin "10") (pinfunction "NC_10") (pintype "passive+no_connect"))
    )
    (net (code "57") (name "unconnected-(IC1-NC_2-Pad7)") (class "Default")
      (node (ref "IC1") (pin "7") (pinfunction "NC_2_7") (pintype "passive+no_connect"))
    )
    (net (code "58") (name "unconnected-(IC1-SCLK{slash}DFS-Pad5)") (class "Default")
      (node (ref "IC1") (pin "5") (pinfunction "SCLK/DFS_5") (pintype "passive+no_connect"))
    )
    (net (code "59") (name "unconnected-(IC1-SDIO{slash}PDWN-Pad6)") (class "Default")
      (node (ref "IC1") (pin "6") (pinfunction "SDIO/PDWN_6") (pintype "passive+no_connect"))
    )
    (net (code "60") (name "unconnected-(IC3-VOUTB-Pad6)") (class "Default")
      (node (ref "IC3") (pin "6") (pinfunction "VOUTB_6") (pintype "passive+no_connect"))
    )
    (net (code "61") (name "unconnected-(J2-Pad12)") (class "Default")
      (node (ref "J2") (pin "12") (pinfunction "12_12") (pintype "passive+no_connect"))
    )
    (net (code "62") (name "unconnected-(U1-com-Pad2)") (class "Default")
      (node (ref "U1") (pin "2") (pinfunction "com_2") (pintype "passive+no_connect"))
    )
    (net (code "63") (name "unconnected-(U2-NC-Pad3)") (class "Default")
      (node (ref "U2") (pin "3") (pinfunction "NC_3") (pintype "passive+no_connect"))
    )
    (net (code "64") (name "unconnected-(U2-NC-Pad6)") (class "Default")
      (node (ref "U2") (pin "6") (pinfunction "NC_6") (pintype "passive+no_connect"))
    )
    (net (code "65") (name "unconnected-(U2-NC-Pad7)") (class "Default")
      (node (ref "U2") (pin "7") (pinfunction "NC_7") (pintype "passive+no_connect"))
    )
  )
)
